# singleLimit.net
KiCad netlist of a schematic drawn in EAGLE
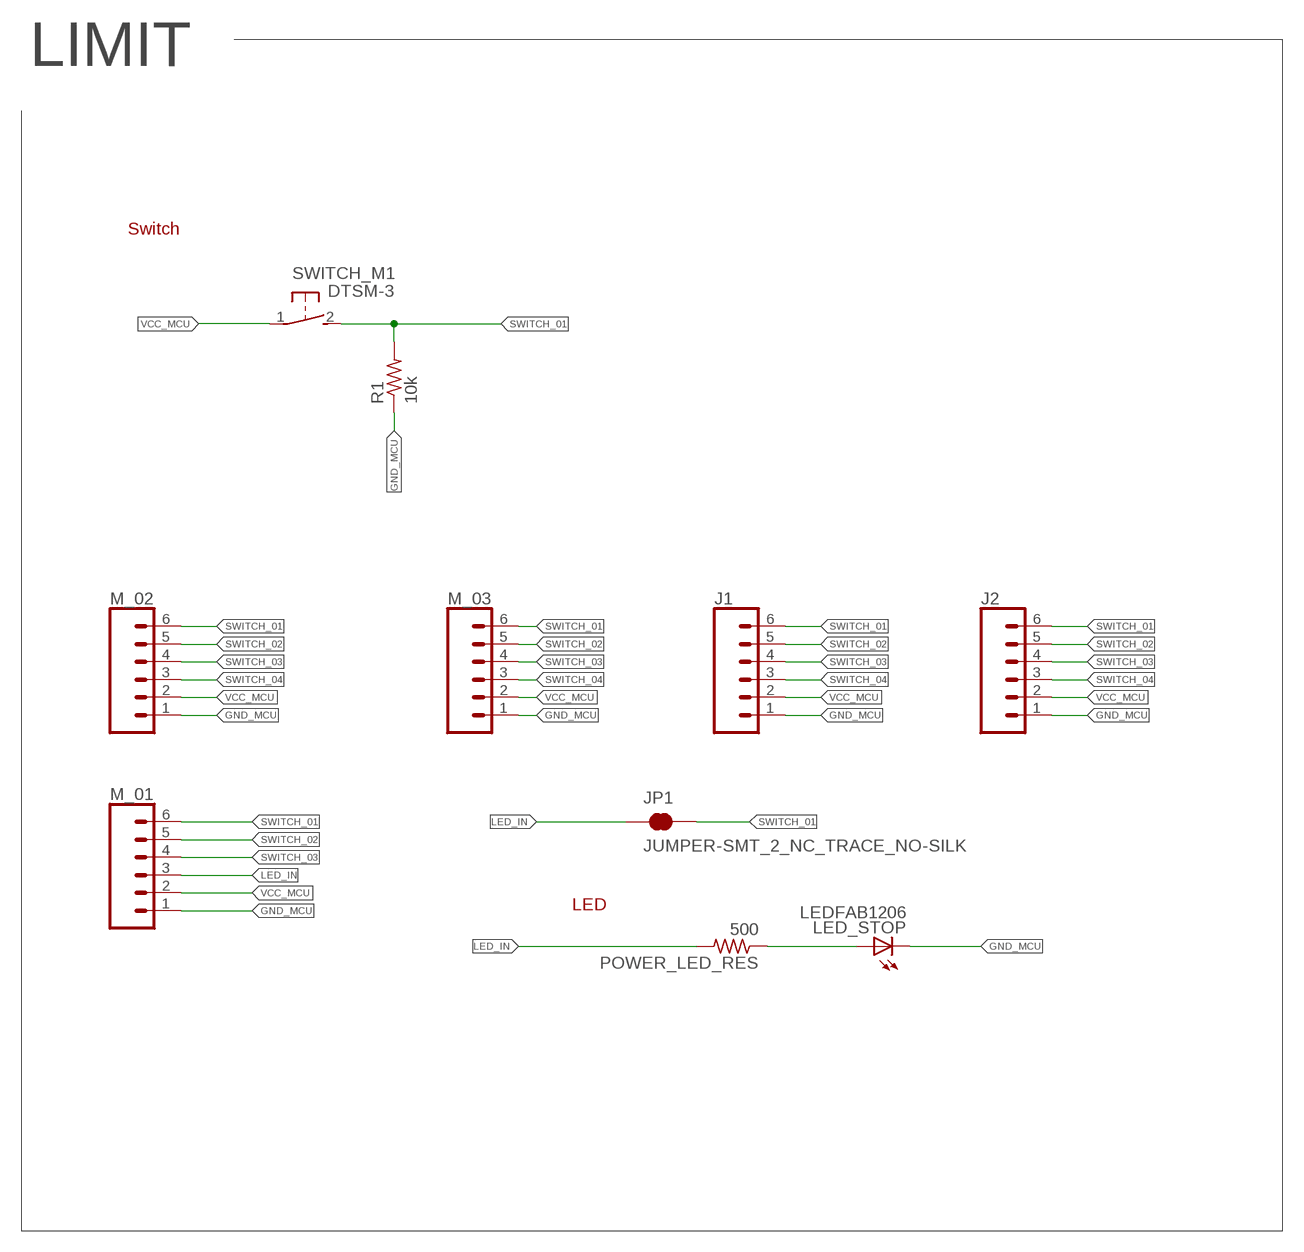
[diagram p0: schematic, sheet 1]

(export (version "E")
  (design (tool "Eeschema 10.0.6"))
  (components
    (comp (ref "J1")
      (value "CONN_06NO_SILK_FEMALE_PTH")
      (footprint "eagle-import:1X06_NO_SILK")
      (libsource (lib "eagle-import") (part "CONN_06NO_SILK_FEMALE_PTH"))
    )
    (comp (ref "J2")
      (value "CONN_06NO_SILK_FEMALE_PTH")
      (footprint "eagle-import:1X06_NO_SILK")
      (libsource (lib "eagle-import") (part "CONN_06NO_SILK_FEMALE_PTH"))
    )
    (comp (ref "JP1")
      (value "JUMPER-SMT_2_NC_TRACE_NO-SILK")
      (footprint "eagle-import:SMT-JUMPER_2_NC_TRACE_NO-SILK")
      (libsource (lib "eagle-import") (part "JUMPER-SMT_2_NC_TRACE_NO-SILK"))
    )
    (comp (ref "LED_STOP")
      (value "LEDFAB1206")
      (footprint "eagle-import:LED1206FAB")
      (libsource (lib "eagle-import") (part "LEDFAB1206"))
    )
    (comp (ref "M_01")
      (value "CONN_06SMD-1MM")
      (footprint "eagle-import:1X06-1MM")
      (libsource (lib "eagle-import") (part "CONN_06SMD-1MM"))
    )
    (comp (ref "M_02")
      (value "CONN_06SMD-1MM")
      (footprint "eagle-import:1X06-1MM")
      (libsource (lib "eagle-import") (part "CONN_06SMD-1MM"))
    )
    (comp (ref "M_03")
      (value "CONN_06SMD-1MM")
      (footprint "eagle-import:1X06-1MM")
      (libsource (lib "eagle-import") (part "CONN_06SMD-1MM"))
    )
    (comp (ref "POWER_LED_RES")
      (value "500")
      (footprint "eagle-import:M0805")
      (libsource (lib "eagle-import") (part "R-US_M0805"))
    )
    (comp (ref "R1")
      (value "10k")
      (footprint "eagle-import:M0805")
      (libsource (lib "eagle-import") (part "R-US_M0805"))
    )
    (comp (ref "SWITCH_M1")
      (value "DTSM-3")
      (footprint "eagle-import:DTSM-3")
      (libsource (lib "eagle-import") (part "DTSM-3"))
    )
  )
  (nets
    (net (code "1") (name "GND_MCU") (class "Default")
      (node (ref "J1") (pin "1") (pinfunction "1_1") (pintype "passive"))
      (node (ref "J2") (pin "1") (pinfunction "1_1") (pintype "passive"))
      (node (ref "LED_STOP") (pin "2") (pinfunction "C_2") (pintype "passive"))
      (node (ref "M_01") (pin "1") (pinfunction "1_1") (pintype "passive"))
      (node (ref "M_02") (pin "1") (pinfunction "1_1") (pintype "passive"))
      (node (ref "M_03") (pin "1") (pinfunction "1_1") (pintype "passive"))
      (node (ref "R1") (pin "1") (pinfunction "1_1") (pintype "passive"))
    )
    (net (code "2") (name "LED_IN") (class "Default")
      (node (ref "JP1") (pin "1") (pinfunction "1_1") (pintype "passive"))
      (node (ref "M_01") (pin "3") (pinfunction "3_3") (pintype "passive"))
      (node (ref "POWER_LED_RES") (pin "2") (pinfunction "2_2") (pintype "passive"))
    )
    (net (code "3") (name "Net-(LED_STOP-A)") (class "Default")
      (node (ref "LED_STOP") (pin "1") (pinfunction "A_1") (pintype "passive"))
      (node (ref "POWER_LED_RES") (pin "1") (pinfunction "1_1") (pintype "passive"))
    )
    (net (code "4") (name "SWITCH_01") (class "Default")
      (node (ref "J1") (pin "6") (pinfunction "6_6") (pintype "passive"))
      (node (ref "J2") (pin "6") (pinfunction "6_6") (pintype "passive"))
      (node (ref "JP1") (pin "2") (pinfunction "2_2") (pintype "passive"))
      (node (ref "M_01") (pin "6") (pinfunction "6_6") (pintype "passive"))
      (node (ref "M_02") (pin "6") (pinfunction "6_6") (pintype "passive"))
      (node (ref "M_03") (pin "6") (pinfunction "6_6") (pintype "passive"))
      (node (ref "R1") (pin "2") (pinfunction "2_2") (pintype "passive"))
      (node (ref "SWITCH_M1") (pin "2") (pinfunction "2_2") (pintype "passive"))
    )
    (net (code "5") (name "SWITCH_02") (class "Default")
      (node (ref "J1") (pin "5") (pinfunction "5_5") (pintype "passive"))
      (node (ref "J2") (pin "5") (pinfunction "5_5") (pintype "passive"))
      (node (ref "M_01") (pin "5") (pinfunction "5_5") (pintype "passive"))
      (node (ref "M_02") (pin "5") (pinfunction "5_5") (pintype "passive"))
      (node (ref "M_03") (pin "5") (pinfunction "5_5") (pintype "passive"))
    )
    (net (code "6") (name "SWITCH_03") (class "Default")
      (node (ref "J1") (pin "4") (pinfunction "4_4") (pintype "passive"))
      (node (ref "J2") (pin "4") (pinfunction "4_4") (pintype "passive"))
      (node (ref "M_01") (pin "4") (pinfunction "4_4") (pintype "passive"))
      (node (ref "M_02") (pin "4") (pinfunction "4_4") (pintype "passive"))
      (node (ref "M_03") (pin "4") (pinfunction "4_4") (pintype "passive"))
    )
    (net (code "7") (name "SWITCH_04") (class "Default")
      (node (ref "J1") (pin "3") (pinfunction "3_3") (pintype "passive"))
      (node (ref "J2") (pin "3") (pinfunction "3_3") (pintype "passive"))
      (node (ref "M_02") (pin "3") (pinfunction "3_3") (pintype "passive"))
      (node (ref "M_03") (pin "3") (pinfunction "3_3") (pintype "passive"))
    )
    (net (code "8") (name "VCC_MCU") (class "Default")
      (node (ref "J1") (pin "2") (pinfunction "2_2") (pintype "passive"))
      (node (ref "J2") (pin "2") (pinfunction "2_2") (pintype "passive"))
      (node (ref "M_01") (pin "2") (pinfunction "2_2") (pintype "passive"))
      (node (ref "M_02") (pin "2") (pinfunction "2_2") (pintype "passive"))
      (node (ref "M_03") (pin "2") (pinfunction "2_2") (pintype "passive"))
      (node (ref "SWITCH_M1") (pin "1") (pinfunction "1_1") (pintype "passive"))
    )
  )
)
